# ttl.net
KiCad netlist of a schematic drawn in Altium Designer
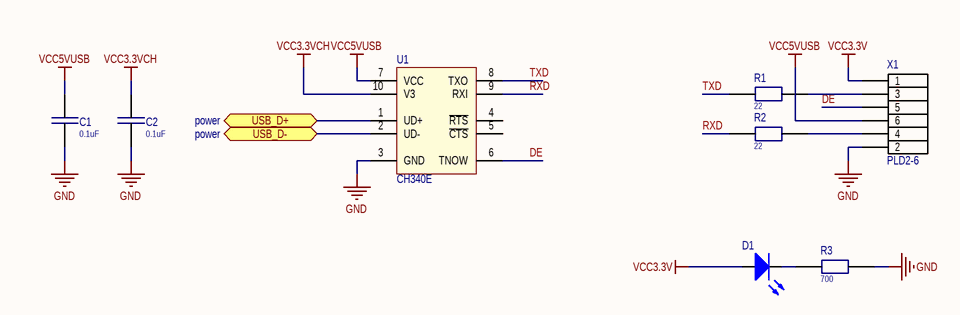
[diagram p0: ttl.SchDoc]

(export (version "E")
  (design (tool "Eeschema 10.0.6"))
  (components
    (comp (ref "C1")
      (value "0.1uF")
      (footprint "C_0603")
      (description "Capacitor")
      (fields (field (name "PART NUMBER") "CC0603KPX7R9BB104"))
      (libsource (lib "capacitors") (part "CAP_SMD"))
    )
    (comp (ref "C2")
      (value "0.1uF")
      (footprint "C_0603")
      (description "Capacitor")
      (fields (field (name "PART NUMBER") "CC0603KPX7R9BB104"))
      (libsource (lib "capacitors") (part "CAP_SMD"))
    )
    (comp (ref "D1")
      (value "RED")
      (footprint "LED_0603")
      (description "LED")
      (fields (field (name "PART NUMBER") "GNL-0603SRC"))
      (libsource (lib "led_lcd") (part "LED_SMT_0603"))
    )
    (comp (ref "R1")
      (value "22")
      (footprint "R_0603")
      (description "Resistor")
      (fields (field (name "PART NUMBER") "RC0603FR-0722RL"))
      (libsource (lib "resistors") (part "RES_SMD"))
    )
    (comp (ref "R2")
      (value "22")
      (footprint "R_0603")
      (description "Resistor")
      (fields (field (name "PART NUMBER") "RC0603FR-0722RL"))
      (libsource (lib "resistors") (part "RES_SMD"))
    )
    (comp (ref "R3")
      (value "700")
      (footprint "R_0603")
      (description "Resistor")
      (fields (field (name "PART NUMBER") "RC0603FR-07750RL"))
      (libsource (lib "resistors") (part "RES_SMD"))
    )
    (comp (ref "U1")
      (value "CH340E")
      (footprint "MSOP10")
      (description "USB to serial chip CH340")
      (fields (field (name "MF") "WCH"))
      (libsource (lib "discret_ic") (part "CH340E"))
    )
    (comp (ref "X1")
      (value "PLD2-6")
      (footprint "PLD-6-sideways")
      (description "Header, 6-Pin, Dual row")
      (libsource (lib "connectors_socets") (part "PLD2-6"))
    )
  )
  (nets
    (net (code "1") (name "/DE") (class "Default")
      (node (ref "U1") (pin "6") (pinfunction "TNOW_6") (pintype "passive"))
      (node (ref "X1") (pin "5") (pinfunction "5_5") (pintype "passive"))
    )
    (net (code "2") (name "/RXD") (class "Default")
      (node (ref "R2") (pin "2") (pinfunction "2_2") (pintype "passive"))
      (node (ref "U1") (pin "9") (pinfunction "RXI_9") (pintype "passive"))
    )
    (net (code "3") (name "/TXD") (class "Default")
      (node (ref "R1") (pin "2") (pinfunction "2_2") (pintype "passive"))
      (node (ref "U1") (pin "8") (pinfunction "TXO_8") (pintype "passive"))
    )
    (net (code "4") (name "/USB_D+") (class "Default")
      (node (ref "U1") (pin "1") (pinfunction "UD+_1") (pintype "passive"))
    )
    (net (code "5") (name "/USB_D-") (class "Default")
      (node (ref "U1") (pin "2") (pinfunction "UD-_2") (pintype "passive"))
    )
    (net (code "6") (name "GND") (class "Default")
      (node (ref "C1") (pin "1") (pinfunction "1_1") (pintype "passive"))
      (node (ref "C2") (pin "1") (pinfunction "1_1") (pintype "passive"))
      (node (ref "R3") (pin "1") (pinfunction "1_1") (pintype "passive"))
      (node (ref "U1") (pin "3") (pinfunction "GND_3") (pintype "passive"))
      (node (ref "X1") (pin "2") (pinfunction "2_2") (pintype "passive"))
    )
    (net (code "7") (name "Net-(D1-K)") (class "Default")
      (node (ref "D1") (pin "2") (pinfunction "K_2") (pintype "passive"))
      (node (ref "R3") (pin "2") (pinfunction "2_2") (pintype "passive"))
    )
    (net (code "8") (name "Net-(R1-Pad1)") (class "Default")
      (node (ref "R1") (pin "1") (pinfunction "1_1") (pintype "passive"))
      (node (ref "X1") (pin "3") (pinfunction "3_3") (pintype "passive"))
    )
    (net (code "9") (name "Net-(R2-Pad1)") (class "Default")
      (node (ref "R2") (pin "1") (pinfunction "1_1") (pintype "passive"))
      (node (ref "X1") (pin "4") (pinfunction "4_4") (pintype "passive"))
    )
    (net (code "10") (name "VCC3.3V") (class "Default")
      (node (ref "D1") (pin "1") (pinfunction "A_1") (pintype "passive"))
      (node (ref "X1") (pin "1") (pinfunction "1_1") (pintype "passive"))
    )
    (net (code "11") (name "VCC3.3VCH") (class "Default")
      (node (ref "C2") (pin "2") (pinfunction "2_2") (pintype "passive"))
      (node (ref "U1") (pin "10") (pinfunction "V3_10") (pintype "passive"))
    )
    (net (code "12") (name "VCC5VUSB") (class "Default")
      (node (ref "C1") (pin "2") (pinfunction "2_2") (pintype "passive"))
      (node (ref "U1") (pin "7") (pinfunction "VCC_7") (pintype "passive"))
      (node (ref "X1") (pin "6") (pinfunction "6_6") (pintype "passive"))
    )
    (net (code "13") (name "unconnected-(U1-~{CTS}-Pad5)") (class "Default")
      (node (ref "U1") (pin "5") (pinfunction "~{CTS}_5") (pintype "passive"))
    )
    (net (code "14") (name "unconnected-(U1-~{RTS}-Pad4)") (class "Default")
      (node (ref "U1") (pin "4") (pinfunction "~{RTS}_4") (pintype "passive"))
    )
  )
)
